# MCU.net
KiCad netlist of a schematic drawn in Altium Designer
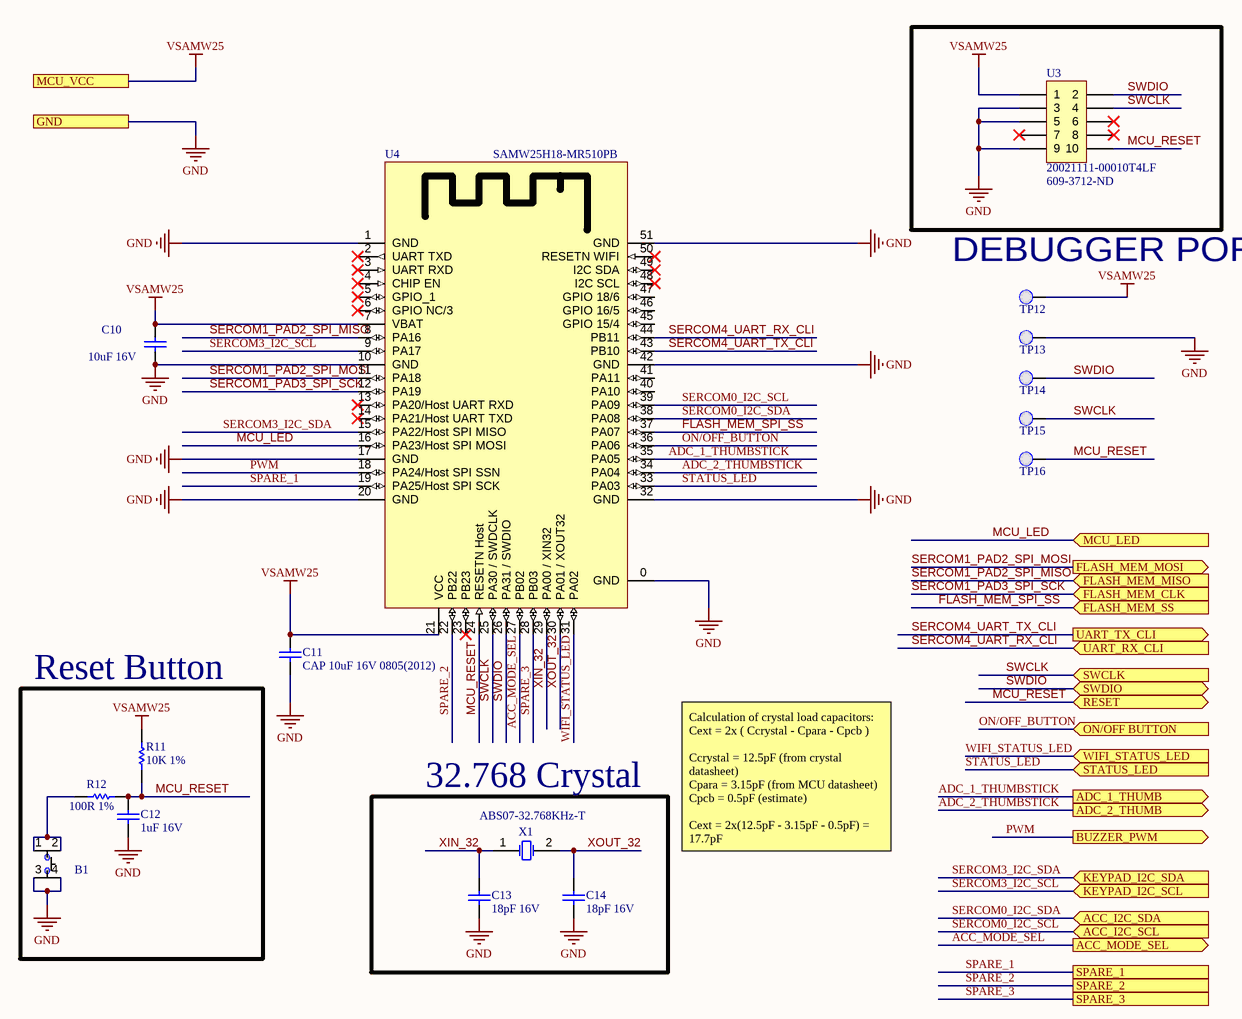
[diagram p0: MCU.SchDoc]

(export (version "E")
  (design (tool "Eeschema 10.0.6"))
  (components
    (comp (ref "B1")
      (value "PTS810 SJK 250 SMTR LFS")
      (footprint "PTS810 SJK 250 SMTR LFS")
      (description "SWITCH TACTILE SPST-NO 0.05A 16V Tactile Switch SPST-NO Top Actuated Surface Mount")
      (fields
        (field (name "MANUFACTURER") "ITT /  C&K Components")
        (field (name "MANUFACTURER PART NUMBER") "PTS810SJK250SMTRLFS")
      )
      (libsource (lib "Schematics") (part "PTS810 SJK 250 SMTR LFS"))
    )
    (comp (ref "C10")
      (value "10uF 16V")
      (footprint "CAPC0805(2012)145_N")
      (description "CAP 10uF 16V ±10% 0805 (2012 Metric) Thickness 1.45mm SMD")
      (fields (field (name "TOLERANCE") "Â±10%"))
      (libsource (lib "Altium Content Vault") (part "CAP"))
    )
    (comp (ref "C11")
      (value "CAP 10uF 16V 0805(2012)")
      (footprint "CAPC0805(2012)145_N")
      (description "CAP 10uF 16V ±10% 0805 (2012 Metric) Thickness 1.45mm SMD")
      (fields (field (name "TOLERANCE") "Â±10%"))
      (libsource (lib "Altium Content Vault") (part "CAP"))
    )
    (comp (ref "C12")
      (value "1uF 16V")
      (footprint "CAPC0603(1608)100_N")
      (description "CAP 1uF 16V ±5% 0603 (1608 Metric) Thickness 1mm SMD")
      (fields (field (name "TOLERANCE") "Â±5%"))
      (libsource (lib "Altium Content Vault") (part "CAP"))
    )
    (comp (ref "C13")
      (value "18pF 16V")
      (footprint "CAPC0603(1608)100_N")
      (description "CAP 18pF 16V ±5% 0603 (1608 Metric) Thickness 1mm SMD")
      (fields (field (name "TOLERANCE") "Â±5%"))
      (libsource (lib "Altium Content Vault") (part "CAP"))
    )
    (comp (ref "C14")
      (value "18pF 16V")
      (footprint "CAPC0603(1608)100_N")
      (description "CAP 18pF 16V ±5% 0603 (1608 Metric) Thickness 1mm SMD")
      (fields (field (name "TOLERANCE") "Â±5%"))
      (libsource (lib "Altium Content Vault") (part "CAP"))
    )
    (comp (ref "R11")
      (value "10K 1%")
      (footprint "RESC0603(1608)_N")
      (description "10K 0.1W 1% 0603 (1608 Metric)  SMD")
      (fields (field (name "POWER") "0.1 W") (field (name "TOLERANCE") "1 %"))
      (libsource (lib "Altium Content Vault") (part "RES"))
    )
    (comp (ref "R12")
      (value "100R 1%")
      (footprint "RESC0603(1608)_N")
      (description "100R 0.1W 1% 0603 (1608 Metric)  SMD")
      (fields (field (name "TOLERANCE") "1 %") (field (name "POWER") "0.1 W"))
      (libsource (lib "Altium Content Vault") (part "RES"))
    )
    (comp (ref "TP12")
      (value "0.1\" Pad")
      (footprint "PCBComponent")
      (libsource (lib "Components - 12.02.20 - 18.05") (part "0.1{dblquote} Pad-A.4"))
    )
    (comp (ref "TP13")
      (value "0.1\" Pad")
      (footprint "PCBComponent")
      (libsource (lib "Components - 12.02.20 - 18.05") (part "0.1{dblquote} Pad-A.4"))
    )
    (comp (ref "TP14")
      (value "0.1\" Pad")
      (footprint "PCBComponent")
      (libsource (lib "Components - 12.02.20 - 18.05") (part "0.1{dblquote} Pad-A.4"))
    )
    (comp (ref "TP15")
      (value "0.1\" Pad")
      (footprint "PCBComponent")
      (libsource (lib "Components - 12.02.20 - 18.05") (part "0.1{dblquote} Pad-A.4"))
    )
    (comp (ref "TP16")
      (value "0.1\" Pad")
      (footprint "PCBComponent")
      (libsource (lib "Components - 12.02.20 - 18.05") (part "0.1{dblquote} Pad-A.4"))
    )
    (comp (ref "U3")
      (value "20021111-00010T4LF")
      (footprint "20021111-00010T4LF")
      (description "CONN HEADER 10POS UNSHD VERT T/H")
      (fields
        (field (name "MANUFACTURER") "Amphenol / FCI")
        (field (name "SUPPLIER PART NUMBER 1") "609-3712-ND")
      )
      (libsource (lib "Schematics") (part "20021111-00010T4LF"))
    )
    (comp (ref "U4")
      (value "SAMW25H18-MR510PB")
      (footprint "SAMW25H18-MR510PB")
      (description "RF TXRX MODULE WIFI TRACE ANT")
      (fields
        (field (name "MANUFACTURER") "Atmel")
        (field (name "MANUFACTURER PART NUMBER") "ATSAMW25H18-MR510PB")
      )
      (libsource (lib "Schematics") (part "SAMW25H18-MR510PB"))
    )
    (comp (ref "X1")
      (value "ABS07-32.768KHz-T")
      (footprint "ABRA-ABS07-2_V")
      (description "Crystal, 32.768 kHz, 12.5 pF, -40 to 85 degC, SMD Low Profile 3.2 x 1.5 x 0.9 mm, Tape and Reel")
      (fields (field (name "MANUFACTURER") "Abracon"))
      (libsource (lib "Altium Content Vault") (part "ABRA-ABS07-2"))
    )
  )
  (nets
    (net (code "1") (name "/ACC_MODE_SEL") (class "Default")
      (node (ref "U4") (pin "27") (pinfunction "PB02_27") (pintype "bidirectional"))
    )
    (net (code "2") (name "/ADC_1_THUMBSTICK") (class "Default")
      (node (ref "U4") (pin "35") (pinfunction "PA05_35") (pintype "bidirectional"))
    )
    (net (code "3") (name "/ADC_2_THUMBSTICK") (class "Default")
      (node (ref "U4") (pin "34") (pinfunction "PA04_34") (pintype "bidirectional"))
    )
    (net (code "4") (name "/FLASH_MEM_SPI_SS") (class "Default")
      (node (ref "U4") (pin "37") (pinfunction "PA07_37") (pintype "bidirectional"))
    )
    (net (code "5") (name "/MCU_LED") (class "Default")
      (node (ref "U4") (pin "16") (pinfunction "PA23/Host_SPI_MOSI_16") (pintype "bidirectional"))
    )
    (net (code "6") (name "/MCU_RESET") (class "Default")
      (node (ref "C12") (pin "2") (pinfunction "2_2") (pintype "passive"))
      (node (ref "R11") (pin "1") (pinfunction "1_1") (pintype "passive"))
      (node (ref "R12") (pin "2") (pinfunction "2_2") (pintype "passive"))
      (node (ref "TP16") (pin "1") (pinfunction "PAD_1") (pintype "passive"))
      (node (ref "U3") (pin "10") (pinfunction "10_10") (pintype "passive"))
      (node (ref "U4") (pin "24") (pinfunction "RESETN_Host_24") (pintype "input"))
    )
    (net (code "7") (name "/ON{slash}OFF_BUTTON") (class "Default")
      (node (ref "U4") (pin "36") (pinfunction "PA06_36") (pintype "bidirectional"))
    )
    (net (code "8") (name "/PWM") (class "Default")
      (node (ref "U4") (pin "18") (pinfunction "PA24/Host_SPI_SSN_18") (pintype "bidirectional"))
    )
    (net (code "9") (name "/SERCOM0_I2C_SCL") (class "Default")
      (node (ref "U4") (pin "39") (pinfunction "PA09_39") (pintype "bidirectional"))
    )
    (net (code "10") (name "/SERCOM0_I2C_SDA") (class "Default")
      (node (ref "U4") (pin "38") (pinfunction "PA08_38") (pintype "bidirectional"))
    )
    (net (code "11") (name "/SERCOM1_PAD2_SPI_MISO") (class "Default")
      (node (ref "U4") (pin "8") (pinfunction "PA16_8") (pintype "bidirectional"))
    )
    (net (code "12") (name "/SERCOM1_PAD2_SPI_MOSI") (class "Default")
      (node (ref "U4") (pin "11") (pinfunction "PA18_11") (pintype "bidirectional"))
    )
    (net (code "13") (name "/SERCOM1_PAD3_SPI_SCK") (class "Default")
      (node (ref "U4") (pin "12") (pinfunction "PA19_12") (pintype "bidirectional"))
    )
    (net (code "14") (name "/SERCOM3_I2C_SCL") (class "Default")
      (node (ref "U4") (pin "9") (pinfunction "PA17_9") (pintype "bidirectional"))
    )
    (net (code "15") (name "/SERCOM3_I2C_SDA") (class "Default")
      (node (ref "U4") (pin "15") (pinfunction "PA22/Host_SPI_MISO_15") (pintype "bidirectional"))
    )
    (net (code "16") (name "/SERCOM4_UART_RX_CLI") (class "Default")
      (node (ref "U4") (pin "44") (pinfunction "PB11_44") (pintype "bidirectional"))
    )
    (net (code "17") (name "/SERCOM4_UART_TX_CLI") (class "Default")
      (node (ref "U4") (pin "43") (pinfunction "PB10_43") (pintype "bidirectional"))
    )
    (net (code "18") (name "/SPARE_1") (class "Default")
      (node (ref "U4") (pin "19") (pinfunction "PA25/Host_SPI_SCK_19") (pintype "bidirectional"))
    )
    (net (code "19") (name "/SPARE_2") (class "Default")
      (node (ref "U4") (pin "22") (pinfunction "PB22_22") (pintype "bidirectional"))
    )
    (net (code "20") (name "/SPARE_3") (class "Default")
      (node (ref "U4") (pin "28") (pinfunction "PB03_28") (pintype "bidirectional"))
    )
    (net (code "21") (name "/STATUS_LED") (class "Default")
      (node (ref "U4") (pin "33") (pinfunction "PA03_33") (pintype "bidirectional"))
    )
    (net (code "22") (name "/SWCLK") (class "Default")
      (node (ref "TP15") (pin "1") (pinfunction "PAD_1") (pintype "passive"))
      (node (ref "U3") (pin "4") (pinfunction "4_4") (pintype "passive"))
      (node (ref "U4") (pin "25") (pinfunction "PA30_/_SWDCLK_25") (pintype "bidirectional"))
    )
    (net (code "23") (name "/SWDIO") (class "Default")
      (node (ref "TP14") (pin "1") (pinfunction "PAD_1") (pintype "passive"))
      (node (ref "U3") (pin "2") (pinfunction "2_2") (pintype "passive"))
      (node (ref "U4") (pin "26") (pinfunction "PA31_/_SWDIO_26") (pintype "bidirectional"))
    )
    (net (code "24") (name "/WIFI_STATUS_LED") (class "Default")
      (node (ref "U4") (pin "31") (pinfunction "PA02_31") (pintype "bidirectional"))
    )
    (net (code "25") (name "/XIN_32") (class "Default")
      (node (ref "C13") (pin "2") (pinfunction "2_2") (pintype "passive"))
      (node (ref "U4") (pin "29") (pinfunction "PA00_/_XIN32_29") (pintype "bidirectional"))
      (node (ref "X1") (pin "1") (pinfunction "X1_1") (pintype "passive"))
    )
    (net (code "26") (name "/XOUT_32") (class "Default")
      (node (ref "C14") (pin "2") (pinfunction "2_2") (pintype "passive"))
      (node (ref "U4") (pin "30") (pinfunction "PA01_/_XOUT32_30") (pintype "bidirectional"))
      (node (ref "X1") (pin "2") (pinfunction "X2_2") (pintype "passive"))
    )
    (net (code "27") (name "GND") (class "Default")
      (node (ref "B1") (pin "3") (pinfunction "3_3") (pintype "power_in"))
      (node (ref "B1") (pin "4") (pinfunction "4_4") (pintype "power_in"))
      (node (ref "C10") (pin "1") (pinfunction "1_1") (pintype "passive"))
      (node (ref "C11") (pin "1") (pinfunction "1_1") (pintype "passive"))
      (node (ref "C12") (pin "1") (pinfunction "1_1") (pintype "passive"))
      (node (ref "C13") (pin "1") (pinfunction "1_1") (pintype "passive"))
      (node (ref "C14") (pin "1") (pinfunction "1_1") (pintype "passive"))
      (node (ref "TP13") (pin "1") (pinfunction "PAD_1") (pintype "passive"))
      (node (ref "U3") (pin "3") (pinfunction "3_3") (pintype "passive"))
      (node (ref "U3") (pin "5") (pinfunction "5_5") (pintype "passive"))
      (node (ref "U3") (pin "9") (pinfunction "9_9") (pintype "passive"))
      (node (ref "U4") (pin "0") (pinfunction "GND_0") (pintype "power_in"))
      (node (ref "U4") (pin "1") (pinfunction "GND_1") (pintype "power_in"))
      (node (ref "U4") (pin "10") (pinfunction "GND_10") (pintype "power_in"))
      (node (ref "U4") (pin "17") (pinfunction "GND_17") (pintype "power_in"))
      (node (ref "U4") (pin "20") (pinfunction "GND_20") (pintype "power_in"))
      (node (ref "U4") (pin "32") (pinfunction "GND_32") (pintype "power_in"))
      (node (ref "U4") (pin "42") (pinfunction "GND_42") (pintype "power_in"))
      (node (ref "U4") (pin "51") (pinfunction "GND_51") (pintype "power_in"))
    )
    (net (code "28") (name "Net-(B1-Pad1)") (class "Default")
      (node (ref "B1") (pin "1") (pinfunction "1_1") (pintype "power_in"))
      (node (ref "B1") (pin "2") (pinfunction "2_2") (pintype "power_in"))
      (node (ref "R12") (pin "1") (pinfunction "1_1") (pintype "passive"))
    )
    (net (code "29") (name "VSAMW25") (class "Default")
      (node (ref "C10") (pin "2") (pinfunction "2_2") (pintype "passive"))
      (node (ref "C11") (pin "2") (pinfunction "2_2") (pintype "passive"))
      (node (ref "R11") (pin "2") (pinfunction "2_2") (pintype "passive"))
      (node (ref "TP12") (pin "1") (pinfunction "PAD_1") (pintype "passive"))
      (node (ref "U3") (pin "1") (pinfunction "1_1") (pintype "passive"))
      (node (ref "U4") (pin "21") (pinfunction "VCC_21") (pintype "power_in"))
      (node (ref "U4") (pin "7") (pinfunction "VBAT_7") (pintype "power_in"))
    )
    (net (code "30") (name "unconnected-(U3-Pad6)") (class "Default")
      (node (ref "U3") (pin "6") (pinfunction "6_6") (pintype "passive+no_connect"))
    )
    (net (code "31") (name "unconnected-(U3-Pad7)") (class "Default")
      (node (ref "U3") (pin "7") (pinfunction "7_7") (pintype "passive+no_connect"))
    )
    (net (code "32") (name "unconnected-(U3-Pad8)") (class "Default")
      (node (ref "U3") (pin "8") (pinfunction "8_8") (pintype "passive+no_connect"))
    )
    (net (code "33") (name "unconnected-(U4-CHIP_EN-Pad4)") (class "Default")
      (node (ref "U4") (pin "4") (pinfunction "CHIP_EN_4") (pintype "input+no_connect"))
    )
    (net (code "34") (name "unconnected-(U4-GPIO_1-Pad5)") (class "Default")
      (node (ref "U4") (pin "5") (pinfunction "GPIO_1_5") (pintype "bidirectional+no_connect"))
    )
    (net (code "35") (name "unconnected-(U4-GPIO_15{slash}4-Pad45)") (class "Default")
      (node (ref "U4") (pin "45") (pinfunction "GPIO_15/4_45") (pintype "bidirectional"))
    )
    (net (code "36") (name "unconnected-(U4-GPIO_16{slash}5-Pad46)") (class "Default")
      (node (ref "U4") (pin "46") (pinfunction "GPIO_16/5_46") (pintype "bidirectional"))
    )
    (net (code "37") (name "unconnected-(U4-GPIO_18{slash}6-Pad47)") (class "Default")
      (node (ref "U4") (pin "47") (pinfunction "GPIO_18/6_47") (pintype "bidirectional"))
    )
    (net (code "38") (name "unconnected-(U4-GPIO_NC{slash}3-Pad6)") (class "Default")
      (node (ref "U4") (pin "6") (pinfunction "GPIO_NC/3_6") (pintype "bidirectional+no_connect"))
    )
    (net (code "39") (name "unconnected-(U4-I2C_SCL-Pad48)") (class "Default")
      (node (ref "U4") (pin "48") (pinfunction "I2C_SCL_48") (pintype "bidirectional+no_connect"))
    )
    (net (code "40") (name "unconnected-(U4-I2C_SDA-Pad49)") (class "Default")
      (node (ref "U4") (pin "49") (pinfunction "I2C_SDA_49") (pintype "bidirectional+no_connect"))
    )
    (net (code "41") (name "unconnected-(U4-PA10-Pad40)") (class "Default")
      (node (ref "U4") (pin "40") (pinfunction "PA10_40") (pintype "bidirectional"))
    )
    (net (code "42") (name "unconnected-(U4-PA11-Pad41)") (class "Default")
      (node (ref "U4") (pin "41") (pinfunction "PA11_41") (pintype "bidirectional"))
    )
    (net (code "43") (name "unconnected-(U4-PA20{slash}Host_UART_RXD-Pad13)") (class "Default")
      (node (ref "U4") (pin "13") (pinfunction "PA20/Host_UART_RXD_13") (pintype "bidirectional+no_connect"))
    )
    (net (code "44") (name "unconnected-(U4-PA21{slash}Host_UART_TXD-Pad14)") (class "Default")
      (node (ref "U4") (pin "14") (pinfunction "PA21/Host_UART_TXD_14") (pintype "bidirectional+no_connect"))
    )
    (net (code "45") (name "unconnected-(U4-PB23-Pad23)") (class "Default")
      (node (ref "U4") (pin "23") (pinfunction "PB23_23") (pintype "bidirectional+no_connect"))
    )
    (net (code "46") (name "unconnected-(U4-RESETN_WIFI-Pad50)") (class "Default")
      (node (ref "U4") (pin "50") (pinfunction "RESETN_WIFI_50") (pintype "input+no_connect"))
    )
    (net (code "47") (name "unconnected-(U4-UART_RXD-Pad3)") (class "Default")
      (node (ref "U4") (pin "3") (pinfunction "UART_RXD_3") (pintype "input+no_connect"))
    )
    (net (code "48") (name "unconnected-(U4-UART_TXD-Pad2)") (class "Default")
      (node (ref "U4") (pin "2") (pinfunction "UART_TXD_2") (pintype "output+no_connect"))
    )
  )
)
